# lichtenstein_pwm_v2.net
KiCad netlist of a schematic drawn in EAGLE
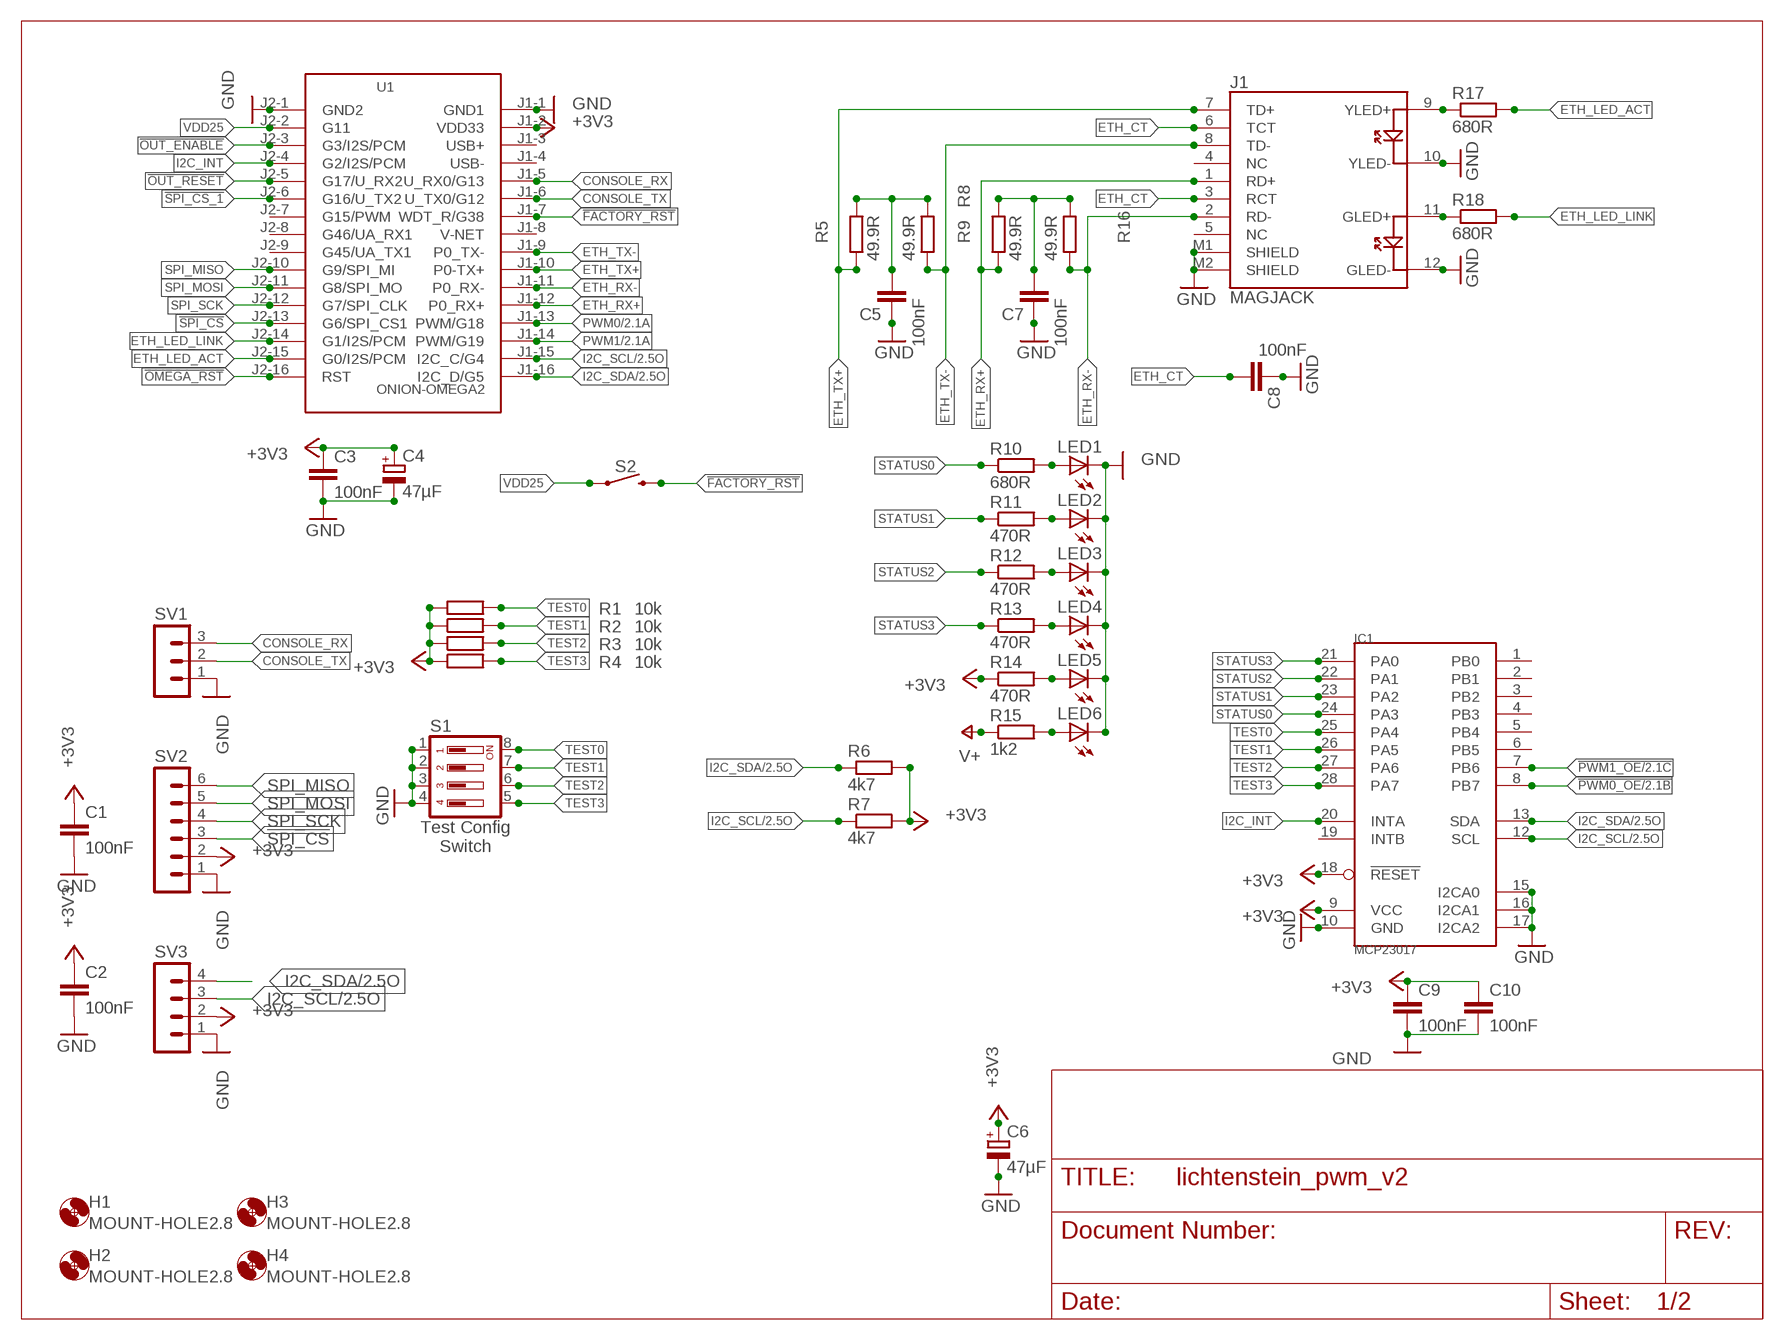
[diagram p0: schematic, sheet 1]
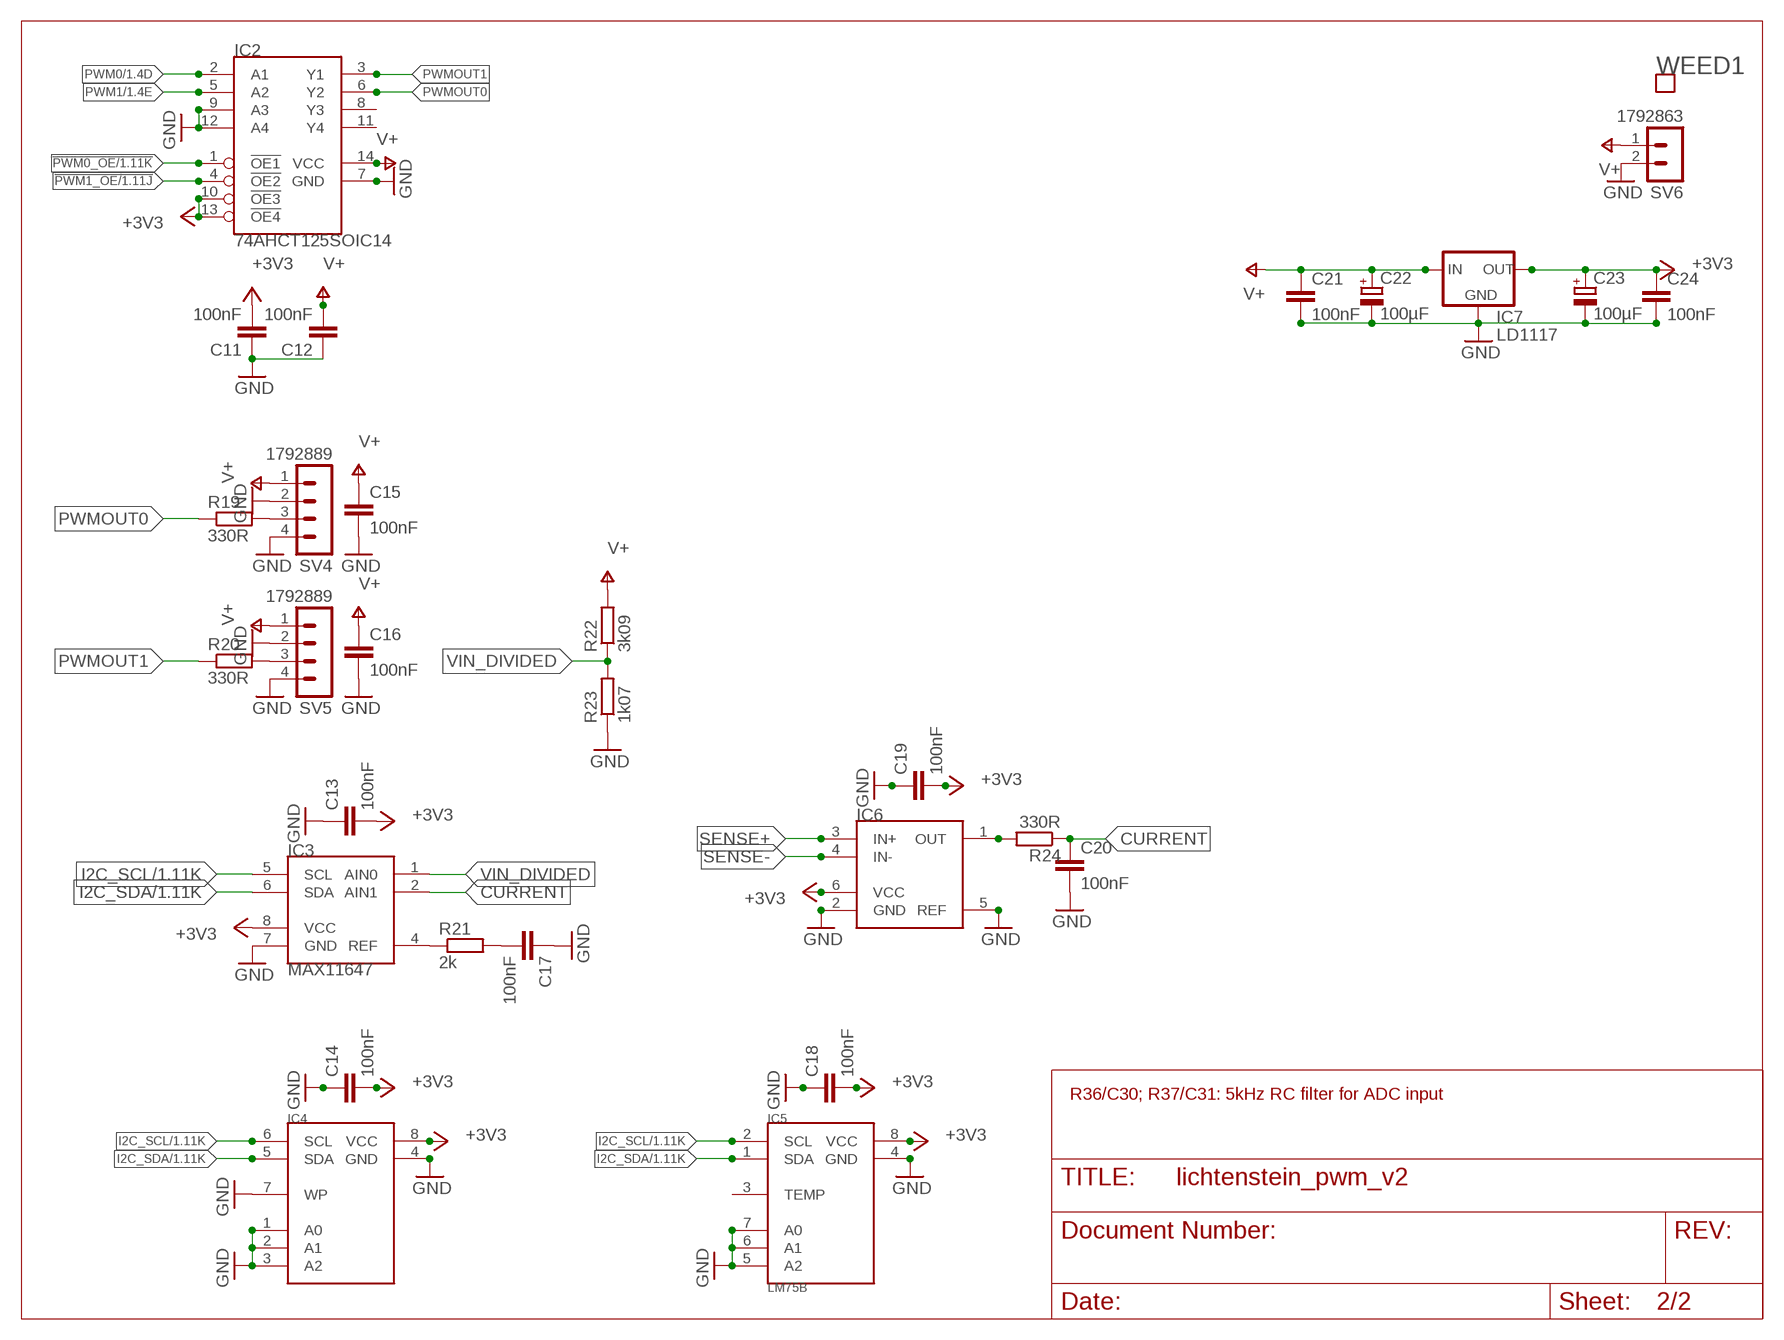
[diagram p1: schematic, sheet 2]

(export (version "E")
  (design (tool "Eeschema 10.0.6"))
  (components
    (comp (ref "C1")
      (value "100nF")
      (footprint "eagle-import:C0805")
      (libsource (lib "eagle-import") (part "C-EUC0805"))
    )
    (comp (ref "C2")
      (value "100nF")
      (footprint "eagle-import:C0805")
      (libsource (lib "eagle-import") (part "C-EUC0805"))
    )
    (comp (ref "C3")
      (value "100nF")
      (footprint "eagle-import:C0805")
      (libsource (lib "eagle-import") (part "C-EUC0805"))
    )
    (comp (ref "C4")
      (value "47µF")
      (footprint "eagle-import:SMC_C")
      (libsource (lib "eagle-import") (part "CPOL-EUSMCC"))
    )
    (comp (ref "C5")
      (value "100nF")
      (footprint "eagle-import:C0805")
      (libsource (lib "eagle-import") (part "C-EUC0805"))
    )
    (comp (ref "C6")
      (value "47µF")
      (footprint "eagle-import:SMC_C")
      (libsource (lib "eagle-import") (part "CPOL-EUSMCC"))
    )
    (comp (ref "C7")
      (value "100nF")
      (footprint "eagle-import:C0805")
      (libsource (lib "eagle-import") (part "C-EUC0805"))
    )
    (comp (ref "C8")
      (value "100nF")
      (footprint "eagle-import:C0805")
      (libsource (lib "eagle-import") (part "C-EUC0805"))
    )
    (comp (ref "C9")
      (value "100nF")
      (footprint "eagle-import:C0805")
      (libsource (lib "eagle-import") (part "C-EUC0805"))
    )
    (comp (ref "C10")
      (value "100nF")
      (footprint "eagle-import:C0805")
      (libsource (lib "eagle-import") (part "C-EUC0805"))
    )
    (comp (ref "H1")
      (value "MOUNT-HOLE2.8")
      (footprint "eagle-import:2,8")
      (libsource (lib "eagle-import") (part "MOUNT-HOLE2.8"))
    )
    (comp (ref "H2")
      (value "MOUNT-HOLE2.8")
      (footprint "eagle-import:2,8")
      (libsource (lib "eagle-import") (part "MOUNT-HOLE2.8"))
    )
    (comp (ref "H3")
      (value "MOUNT-HOLE2.8")
      (footprint "eagle-import:2,8")
      (libsource (lib "eagle-import") (part "MOUNT-HOLE2.8"))
    )
    (comp (ref "H4")
      (value "MOUNT-HOLE2.8")
      (footprint "eagle-import:2,8")
      (libsource (lib "eagle-import") (part "MOUNT-HOLE2.8"))
    )
    (comp (ref "IC1")
      (value "MCP23017")
      (footprint "eagle-import:SO28W")
      (libsource (lib "eagle-import") (part "MCP23017SOIC28"))
    )
    (comp (ref "J1")
      (value "MAGJACK")
      (footprint "eagle-import:MAGJACK")
      (libsource (lib "eagle-import") (part "MAGJACK"))
    )
    (comp (ref "LED1")
      (value "LEDCHIPLED_1206")
      (footprint "eagle-import:CHIPLED_1206")
      (libsource (lib "eagle-import") (part "LEDCHIPLED_1206"))
    )
    (comp (ref "LED2")
      (value "LEDCHIPLED_1206")
      (footprint "eagle-import:CHIPLED_1206")
      (libsource (lib "eagle-import") (part "LEDCHIPLED_1206"))
    )
    (comp (ref "LED3")
      (value "LEDCHIPLED_1206")
      (footprint "eagle-import:CHIPLED_1206")
      (libsource (lib "eagle-import") (part "LEDCHIPLED_1206"))
    )
    (comp (ref "LED4")
      (value "LEDCHIPLED_1206")
      (footprint "eagle-import:CHIPLED_1206")
      (libsource (lib "eagle-import") (part "LEDCHIPLED_1206"))
    )
    (comp (ref "LED5")
      (value "LEDCHIPLED_1206")
      (footprint "eagle-import:CHIPLED_1206")
      (libsource (lib "eagle-import") (part "LEDCHIPLED_1206"))
    )
    (comp (ref "LED6")
      (value "LEDCHIPLED_1206")
      (footprint "eagle-import:CHIPLED_1206")
      (libsource (lib "eagle-import") (part "LEDCHIPLED_1206"))
    )
    (comp (ref "R1")
      (value "10k")
      (footprint "eagle-import:M0805")
      (libsource (lib "eagle-import") (part "R-EU_M0805"))
    )
    (comp (ref "R2")
      (value "10k")
      (footprint "eagle-import:M0805")
      (libsource (lib "eagle-import") (part "R-EU_M0805"))
    )
    (comp (ref "R3")
      (value "10k")
      (footprint "eagle-import:M0805")
      (libsource (lib "eagle-import") (part "R-EU_M0805"))
    )
    (comp (ref "R4")
      (value "10k")
      (footprint "eagle-import:M0805")
      (libsource (lib "eagle-import") (part "R-EU_M0805"))
    )
    (comp (ref "R5")
      (value "49.9R")
      (footprint "eagle-import:M0805")
      (libsource (lib "eagle-import") (part "R-EU_M0805"))
    )
    (comp (ref "R6")
      (value "4k7")
      (footprint "eagle-import:M0805")
      (libsource (lib "eagle-import") (part "R-EU_M0805"))
    )
    (comp (ref "R7")
      (value "4k7")
      (footprint "eagle-import:M0805")
      (libsource (lib "eagle-import") (part "R-EU_M0805"))
    )
    (comp (ref "R8")
      (value "49.9R")
      (footprint "eagle-import:M0805")
      (libsource (lib "eagle-import") (part "R-EU_M0805"))
    )
    (comp (ref "R9")
      (value "49.9R")
      (footprint "eagle-import:M0805")
      (libsource (lib "eagle-import") (part "R-EU_M0805"))
    )
    (comp (ref "R10")
      (value "680R")
      (footprint "eagle-import:M0805")
      (libsource (lib "eagle-import") (part "R-EU_M0805"))
    )
    (comp (ref "R11")
      (value "470R")
      (footprint "eagle-import:M0805")
      (libsource (lib "eagle-import") (part "R-EU_M0805"))
    )
    (comp (ref "R12")
      (value "470R")
      (footprint "eagle-import:M0805")
      (libsource (lib "eagle-import") (part "R-EU_M0805"))
    )
    (comp (ref "R13")
      (value "470R")
      (footprint "eagle-import:M0805")
      (libsource (lib "eagle-import") (part "R-EU_M0805"))
    )
    (comp (ref "R14")
      (value "470R")
      (footprint "eagle-import:M0805")
      (libsource (lib "eagle-import") (part "R-EU_M0805"))
    )
    (comp (ref "R15")
      (value "1k2")
      (footprint "eagle-import:M0805")
      (libsource (lib "eagle-import") (part "R-EU_M0805"))
    )
    (comp (ref "R16")
      (value "49.9R")
      (footprint "eagle-import:M0805")
      (libsource (lib "eagle-import") (part "R-EU_M0805"))
    )
    (comp (ref "R17")
      (value "680R")
      (footprint "eagle-import:M0805")
      (libsource (lib "eagle-import") (part "R-EU_M0805"))
    )
    (comp (ref "R18")
      (value "680R")
      (footprint "eagle-import:M0805")
      (libsource (lib "eagle-import") (part "R-EU_M0805"))
    )
    (comp (ref "S1")
      (value "219-04")
      (footprint "eagle-import:CTS-219-04")
      (libsource (lib "eagle-import") (part "219-04"))
    )
    (comp (ref "S2")
      (value "MOMENTARY-SWITCH-SPST-PTH-6.0MM")
      (footprint "eagle-import:TACTILE_SWITCH_PTH_6.0MM")
      (libsource (lib "eagle-import") (part "MOMENTARY-SWITCH-SPST-PTH-6.0MM"))
    )
    (comp (ref "SV1")
      (value "MA03-1")
      (footprint "eagle-import:MA03-1")
      (libsource (lib "eagle-import") (part "MA03-1"))
    )
    (comp (ref "SV2")
      (value "MA06-1")
      (footprint "eagle-import:MA06-1")
      (libsource (lib "eagle-import") (part "MA06-1"))
    )
    (comp (ref "SV3")
      (value "MA04-1")
      (footprint "eagle-import:MA04-1")
      (libsource (lib "eagle-import") (part "MA04-1"))
    )
    (comp (ref "U1")
      (value "ONION-OMEGA2")
      (footprint "eagle-import:ONION-2MM-2X16")
      (libsource (lib "eagle-import") (part "ONION-OMEGA2"))
    )
    (comp (ref "C11")
      (value "100nF")
      (footprint "eagle-import:C0805")
      (libsource (lib "eagle-import") (part "C-EUC0805"))
    )
    (comp (ref "C12")
      (value "100nF")
      (footprint "eagle-import:C0805")
      (libsource (lib "eagle-import") (part "C-EUC0805"))
    )
    (comp (ref "C13")
      (value "100nF")
      (footprint "eagle-import:C0805")
      (libsource (lib "eagle-import") (part "C-EUC0805"))
    )
    (comp (ref "C14")
      (value "100nF")
      (footprint "eagle-import:C0805")
      (libsource (lib "eagle-import") (part "C-EUC0805"))
    )
    (comp (ref "C15")
      (value "100nF")
      (footprint "eagle-import:C0805")
      (libsource (lib "eagle-import") (part "C-EUC0805"))
    )
    (comp (ref "C16")
      (value "100nF")
      (footprint "eagle-import:C0805")
      (libsource (lib "eagle-import") (part "C-EUC0805"))
    )
    (comp (ref "C17")
      (value "100nF")
      (footprint "eagle-import:C0805")
      (libsource (lib "eagle-import") (part "C-EUC0805"))
    )
    (comp (ref "C18")
      (value "100nF")
      (footprint "eagle-import:C0805")
      (libsource (lib "eagle-import") (part "C-EUC0805"))
    )
    (comp (ref "C19")
      (value "100nF")
      (footprint "eagle-import:C0805")
      (libsource (lib "eagle-import") (part "C-EUC0805"))
    )
    (comp (ref "C20")
      (value "100nF")
      (footprint "eagle-import:C0805")
      (libsource (lib "eagle-import") (part "C-EUC0805"))
    )
    (comp (ref "C21")
      (value "100nF")
      (footprint "eagle-import:C0805")
      (libsource (lib "eagle-import") (part "C-EUC0805"))
    )
    (comp (ref "C22")
      (value "100µF")
      (footprint "eagle-import:PANASONIC_D")
      (libsource (lib "eagle-import") (part "CPOL-EUD"))
    )
    (comp (ref "C23")
      (value "100µF")
      (footprint "eagle-import:CT7343")
      (libsource (lib "eagle-import") (part "CPOL-EUCT7343"))
    )
    (comp (ref "C24")
      (value "100nF")
      (footprint "eagle-import:C0805")
      (libsource (lib "eagle-import") (part "C-EUC0805"))
    )
    (comp (ref "IC2")
      (value "74AHCT125SOIC14")
      (footprint "eagle-import:SO14")
      (libsource (lib "eagle-import") (part "74AHCT125SOIC14"))
    )
    (comp (ref "IC3")
      (value "MAX11647")
      (footprint "eagle-import:UMAX8")
      (libsource (lib "eagle-import") (part "MAX11647UMAX-8"))
    )
    (comp (ref "IC4")
      (value "AT24C02DSOIC-8")
      (footprint "eagle-import:SOIC8")
      (libsource (lib "eagle-import") (part "AT24C02DSOIC-8"))
    )
    (comp (ref "IC5")
      (value "LM75B")
      (footprint "eagle-import:SOIC8")
      (libsource (lib "eagle-import") (part "LM75B"))
    )
    (comp (ref "IC6")
      (value "INA18120VVSOT-23")
      (footprint "eagle-import:SOT23-6L")
      (libsource (lib "eagle-import") (part "INA181SOT-2320VV"))
    )
    (comp (ref "IC7")
      (value "LD1117")
      (footprint "eagle-import:TO220V")
      (libsource (lib "eagle-import") (part "LD1117TO-220"))
    )
    (comp (ref "R19")
      (value "330R")
      (footprint "eagle-import:M0805")
      (libsource (lib "eagle-import") (part "R-EU_M0805"))
    )
    (comp (ref "R20")
      (value "330R")
      (footprint "eagle-import:M0805")
      (libsource (lib "eagle-import") (part "R-EU_M0805"))
    )
    (comp (ref "R21")
      (value "2k")
      (footprint "eagle-import:M0805")
      (libsource (lib "eagle-import") (part "R-EU_M0805"))
    )
    (comp (ref "R22")
      (value "3k09")
      (footprint "eagle-import:M0805")
      (libsource (lib "eagle-import") (part "R-EU_M0805"))
    )
    (comp (ref "R23")
      (value "1k07")
      (footprint "eagle-import:M0805")
      (libsource (lib "eagle-import") (part "R-EU_M0805"))
    )
    (comp (ref "R24")
      (value "330R")
      (footprint "eagle-import:M0805")
      (libsource (lib "eagle-import") (part "R-EU_M0805"))
    )
    (comp (ref "SV4")
      (value "1792889")
      (footprint "eagle-import:1792889")
      (libsource (lib "eagle-import") (part "1792889"))
    )
    (comp (ref "SV5")
      (value "1792889")
      (footprint "eagle-import:1792889")
      (libsource (lib "eagle-import") (part "1792889"))
    )
    (comp (ref "SV6")
      (value "1792863")
      (footprint "eagle-import:1792863")
      (libsource (lib "eagle-import") (part "1792863"))
    )
    (comp (ref "WEED1")
      (value "WEED")
      (footprint "eagle-import:DOINK")
      (libsource (lib "eagle-import") (part "WEED"))
    )
  )
  (nets
    (net (code "1") (name "+3V3") (class "Default")
      (node (ref "C1") (pin "1") (pinfunction "1_1") (pintype "passive"))
      (node (ref "C10") (pin "1") (pinfunction "1_1") (pintype "passive"))
      (node (ref "C11") (pin "2") (pinfunction "2_2") (pintype "passive"))
      (node (ref "C13") (pin "2") (pinfunction "2_2") (pintype "passive"))
      (node (ref "C14") (pin "2") (pinfunction "2_2") (pintype "passive"))
      (node (ref "C18") (pin "2") (pinfunction "2_2") (pintype "passive"))
      (node (ref "C19") (pin "2") (pinfunction "2_2") (pintype "passive"))
      (node (ref "C2") (pin "1") (pinfunction "1_1") (pintype "passive"))
      (node (ref "C23") (pin "+") (pinfunction "+_+") (pintype "passive"))
      (node (ref "C24") (pin "1") (pinfunction "1_1") (pintype "passive"))
      (node (ref "C3") (pin "1") (pinfunction "1_1") (pintype "passive"))
      (node (ref "C4") (pin "+") (pinfunction "+_+") (pintype "passive"))
      (node (ref "C6") (pin "+") (pinfunction "+_+") (pintype "passive"))
      (node (ref "C9") (pin "1") (pinfunction "1_1") (pintype "passive"))
      (node (ref "IC1") (pin "18") (pinfunction "~{RESET}_18") (pintype "input"))
      (node (ref "IC1") (pin "9") (pinfunction "VCC_9") (pintype "power_in"))
      (node (ref "IC2") (pin "10") (pinfunction "~{OE3}_10") (pintype "input"))
      (node (ref "IC2") (pin "13") (pinfunction "~{OE4}_13") (pintype "input"))
      (node (ref "IC3") (pin "8") (pinfunction "VCC_8") (pintype "power_in"))
      (node (ref "IC4") (pin "8") (pinfunction "VCC_8") (pintype "power_in"))
      (node (ref "IC5") (pin "8") (pinfunction "VCC_8") (pintype "power_in"))
      (node (ref "IC6") (pin "6") (pinfunction "VCC_6") (pintype "power_in"))
      (node (ref "IC7") (pin "2") (pinfunction "OUT_2") (pintype "passive"))
      (node (ref "R1") (pin "1") (pinfunction "1_1") (pintype "passive"))
      (node (ref "R14") (pin "1") (pinfunction "1_1") (pintype "passive"))
      (node (ref "R2") (pin "1") (pinfunction "1_1") (pintype "passive"))
      (node (ref "R3") (pin "1") (pinfunction "1_1") (pintype "passive"))
      (node (ref "R4") (pin "1") (pinfunction "1_1") (pintype "passive"))
      (node (ref "R6") (pin "2") (pinfunction "2_2") (pintype "passive"))
      (node (ref "R7") (pin "2") (pinfunction "2_2") (pintype "passive"))
      (node (ref "SV2") (pin "2") (pinfunction "2_2") (pintype "passive"))
      (node (ref "SV3") (pin "2") (pinfunction "2_2") (pintype "passive"))
      (node (ref "U1") (pin "J1-2") (pinfunction "VDD33_J1-2") (pintype "bidirectional"))
    )
    (net (code "2") (name "CONSOLE_RX") (class "Default")
      (node (ref "SV1") (pin "3") (pinfunction "3_3") (pintype "passive"))
      (node (ref "U1") (pin "J1-5") (pinfunction "U_RX0/G13_J1-5") (pintype "bidirectional"))
    )
    (net (code "3") (name "CONSOLE_TX") (class "Default")
      (node (ref "SV1") (pin "2") (pinfunction "2_2") (pintype "passive"))
      (node (ref "U1") (pin "J1-6") (pinfunction "U_TX0/G12_J1-6") (pintype "bidirectional"))
    )
    (net (code "4") (name "CURRENT") (class "Default")
      (node (ref "C20") (pin "1") (pinfunction "1_1") (pintype "passive"))
      (node (ref "IC3") (pin "2") (pinfunction "AIN1_2") (pintype "input"))
      (node (ref "R24") (pin "1") (pinfunction "1_1") (pintype "passive"))
    )
    (net (code "5") (name "ETH_CT") (class "Default")
      (node (ref "C8") (pin "2") (pinfunction "2_2") (pintype "passive"))
      (node (ref "J1") (pin "3") (pinfunction "RCT_3") (pintype "bidirectional"))
      (node (ref "J1") (pin "6") (pinfunction "TCT_6") (pintype "bidirectional"))
    )
    (net (code "6") (name "ETH_LED_ACT") (class "Default")
      (node (ref "R17") (pin "2") (pinfunction "2_2") (pintype "passive"))
      (node (ref "U1") (pin "J2-15") (pinfunction "G0/I2S/PCM_J2-15") (pintype "bidirectional"))
    )
    (net (code "7") (name "ETH_LED_LINK") (class "Default")
      (node (ref "R18") (pin "2") (pinfunction "2_2") (pintype "passive"))
      (node (ref "U1") (pin "J2-14") (pinfunction "G1/I2S/PCM_J2-14") (pintype "bidirectional"))
    )
    (net (code "8") (name "ETH_RX+") (class "Default")
      (node (ref "J1") (pin "1") (pinfunction "RD+_1") (pintype "bidirectional"))
      (node (ref "R9") (pin "1") (pinfunction "1_1") (pintype "passive"))
      (node (ref "U1") (pin "J1-12") (pinfunction "P0_RX+_J1-12") (pintype "bidirectional"))
    )
    (net (code "9") (name "ETH_RX-") (class "Default")
      (node (ref "J1") (pin "2") (pinfunction "RD-_2") (pintype "bidirectional"))
      (node (ref "R16") (pin "1") (pinfunction "1_1") (pintype "passive"))
      (node (ref "U1") (pin "J1-11") (pinfunction "P0_RX-_J1-11") (pintype "bidirectional"))
    )
    (net (code "10") (name "ETH_TX+") (class "Default")
      (node (ref "J1") (pin "7") (pinfunction "TD+_7") (pintype "bidirectional"))
      (node (ref "R5") (pin "1") (pinfunction "1_1") (pintype "passive"))
      (node (ref "U1") (pin "J1-10") (pinfunction "P0-TX+_J1-10") (pintype "bidirectional"))
    )
    (net (code "11") (name "ETH_TX-") (class "Default")
      (node (ref "J1") (pin "8") (pinfunction "TD-_8") (pintype "bidirectional"))
      (node (ref "R8") (pin "1") (pinfunction "1_1") (pintype "passive"))
      (node (ref "U1") (pin "J1-9") (pinfunction "P0_TX-_J1-9") (pintype "bidirectional"))
    )
    (net (code "12") (name "GND") (class "Default")
      (node (ref "C1") (pin "2") (pinfunction "2_2") (pintype "passive"))
      (node (ref "C10") (pin "2") (pinfunction "2_2") (pintype "passive"))
      (node (ref "C11") (pin "1") (pinfunction "1_1") (pintype "passive"))
      (node (ref "C12") (pin "1") (pinfunction "1_1") (pintype "passive"))
      (node (ref "C13") (pin "1") (pinfunction "1_1") (pintype "passive"))
      (node (ref "C14") (pin "1") (pinfunction "1_1") (pintype "passive"))
      (node (ref "C15") (pin "2") (pinfunction "2_2") (pintype "passive"))
      (node (ref "C16") (pin "2") (pinfunction "2_2") (pintype "passive"))
      (node (ref "C17") (pin "1") (pinfunction "1_1") (pintype "passive"))
      (node (ref "C18") (pin "1") (pinfunction "1_1") (pintype "passive"))
      (node (ref "C19") (pin "1") (pinfunction "1_1") (pintype "passive"))
      (node (ref "C2") (pin "2") (pinfunction "2_2") (pintype "passive"))
      (node (ref "C20") (pin "2") (pinfunction "2_2") (pintype "passive"))
      (node (ref "C21") (pin "2") (pinfunction "2_2") (pintype "passive"))
      (node (ref "C22") (pin "-") (pinfunction "-_-") (pintype "passive"))
      (node (ref "C23") (pin "-") (pinfunction "-_-") (pintype "passive"))
      (node (ref "C24") (pin "2") (pinfunction "2_2") (pintype "passive"))
      (node (ref "C3") (pin "2") (pinfunction "2_2") (pintype "passive"))
      (node (ref "C4") (pin "-") (pinfunction "-_-") (pintype "passive"))
      (node (ref "C5") (pin "1") (pinfunction "1_1") (pintype "passive"))
      (node (ref "C6") (pin "-") (pinfunction "-_-") (pintype "passive"))
      (node (ref "C7") (pin "1") (pinfunction "1_1") (pintype "passive"))
      (node (ref "C8") (pin "1") (pinfunction "1_1") (pintype "passive"))
      (node (ref "C9") (pin "2") (pinfunction "2_2") (pintype "passive"))
      (node (ref "IC1") (pin "10") (pinfunction "GND_10") (pintype "power_in"))
      (node (ref "IC1") (pin "15") (pinfunction "I2CA0_15") (pintype "bidirectional"))
      (node (ref "IC1") (pin "16") (pinfunction "I2CA1_16") (pintype "bidirectional"))
      (node (ref "IC1") (pin "17") (pinfunction "I2CA2_17") (pintype "bidirectional"))
      (node (ref "IC2") (pin "12") (pinfunction "A4_12") (pintype "input"))
      (node (ref "IC2") (pin "7") (pinfunction "GND_7") (pintype "power_in"))
      (node (ref "IC2") (pin "9") (pinfunction "A3_9") (pintype "input"))
      (node (ref "IC3") (pin "7") (pinfunction "GND_7") (pintype "power_in"))
      (node (ref "IC4") (pin "1") (pinfunction "A0_1") (pintype "bidirectional"))
      (node (ref "IC4") (pin "2") (pinfunction "A1_2") (pintype "bidirectional"))
      (node (ref "IC4") (pin "3") (pinfunction "A2_3") (pintype "bidirectional"))
      (node (ref "IC4") (pin "4") (pinfunction "GND_4") (pintype "power_in"))
      (node (ref "IC4") (pin "7") (pinfunction "WP_7") (pintype "bidirectional"))
      (node (ref "IC5") (pin "4") (pinfunction "GND_4") (pintype "power_in"))
      (node (ref "IC5") (pin "5") (pinfunction "A2_5") (pintype "bidirectional"))
      (node (ref "IC5") (pin "6") (pinfunction "A1_6") (pintype "bidirectional"))
      (node (ref "IC5") (pin "7") (pinfunction "A0_7") (pintype "bidirectional"))
      (node (ref "IC6") (pin "2") (pinfunction "GND_2") (pintype "power_in"))
      (node (ref "IC6") (pin "5") (pinfunction "REF_5") (pintype "output"))
      (node (ref "IC7") (pin "1") (pinfunction "GND_1") (pintype "input"))
      (node (ref "J1") (pin "10") (pinfunction "YLED-_10") (pintype "bidirectional"))
      (node (ref "J1") (pin "12") (pinfunction "GLED-_12") (pintype "bidirectional"))
      (node (ref "J1") (pin "M1") (pinfunction "SHIELD_M1") (pintype "bidirectional"))
      (node (ref "J1") (pin "M2") (pinfunction "SHIELD_M2") (pintype "bidirectional"))
      (node (ref "LED1") (pin "C") (pinfunction "C_C") (pintype "passive"))
      (node (ref "LED2") (pin "C") (pinfunction "C_C") (pintype "passive"))
      (node (ref "LED3") (pin "C") (pinfunction "C_C") (pintype "passive"))
      (node (ref "LED4") (pin "C") (pinfunction "C_C") (pintype "passive"))
      (node (ref "LED5") (pin "C") (pinfunction "C_C") (pintype "passive"))
      (node (ref "LED6") (pin "C") (pinfunction "C_C") (pintype "passive"))
      (node (ref "R23") (pin "1") (pinfunction "1_1") (pintype "passive"))
      (node (ref "S1") (pin "1") (pinfunction "1_1") (pintype "passive"))
      (node (ref "S1") (pin "2") (pinfunction "2_2") (pintype "passive"))
      (node (ref "S1") (pin "3") (pinfunction "3_3") (pintype "passive"))
      (node (ref "S1") (pin "4") (pinfunction "4_4") (pintype "passive"))
      (node (ref "SV1") (pin "1") (pinfunction "1_1") (pintype "passive"))
      (node (ref "SV2") (pin "1") (pinfunction "1_1") (pintype "passive"))
      (node (ref "SV3") (pin "1") (pinfunction "1_1") (pintype "passive"))
      (node (ref "SV4") (pin "2") (pinfunction "2_2") (pintype "passive"))
      (node (ref "SV4") (pin "4") (pinfunction "4_4") (pintype "passive"))
      (node (ref "SV5") (pin "2") (pinfunction "2_2") (pintype "passive"))
      (node (ref "SV5") (pin "4") (pinfunction "4_4") (pintype "passive"))
      (node (ref "SV6") (pin "2") (pinfunction "2_2") (pintype "passive"))
      (node (ref "U1") (pin "J1-1") (pinfunction "GND1_J1-1") (pintype "bidirectional"))
      (node (ref "U1") (pin "J2-1") (pinfunction "GND2_J2-1") (pintype "bidirectional"))
    )
    (net (code "13") (name "I2C_INT") (class "Default")
      (node (ref "IC1") (pin "20") (pinfunction "INTA_20") (pintype "output"))
      (node (ref "U1") (pin "J2-4") (pinfunction "G2/I2S/PCM_J2-4") (pintype "bidirectional"))
    )
    (net (code "14") (name "I2C_SCL") (class "Default")
      (node (ref "IC1") (pin "12") (pinfunction "SCL_12") (pintype "bidirectional"))
      (node (ref "IC3") (pin "5") (pinfunction "SCL_5") (pintype "bidirectional"))
      (node (ref "IC4") (pin "6") (pinfunction "SCL_6") (pintype "bidirectional"))
      (node (ref "IC5") (pin "2") (pinfunction "SCL_2") (pintype "bidirectional"))
      (node (ref "R7") (pin "1") (pinfunction "1_1") (pintype "passive"))
      (node (ref "SV3") (pin "3") (pinfunction "3_3") (pintype "passive"))
      (node (ref "U1") (pin "J1-15") (pinfunction "I2C_C/G4_J1-15") (pintype "bidirectional"))
    )
    (net (code "15") (name "I2C_SDA") (class "Default")
      (node (ref "IC1") (pin "13") (pinfunction "SDA_13") (pintype "bidirectional"))
      (node (ref "IC3") (pin "6") (pinfunction "SDA_6") (pintype "bidirectional"))
      (node (ref "IC4") (pin "5") (pinfunction "SDA_5") (pintype "bidirectional"))
      (node (ref "IC5") (pin "1") (pinfunction "SDA_1") (pintype "bidirectional"))
      (node (ref "R6") (pin "1") (pinfunction "1_1") (pintype "passive"))
      (node (ref "SV3") (pin "4") (pinfunction "4_4") (pintype "passive"))
      (node (ref "U1") (pin "J1-16") (pinfunction "I2C_D/G5_J1-16") (pintype "bidirectional"))
    )
    (net (code "16") (name "Net-(C5-Pad2)") (class "Default")
      (node (ref "C5") (pin "2") (pinfunction "2_2") (pintype "passive"))
      (node (ref "R5") (pin "2") (pinfunction "2_2") (pintype "passive"))
      (node (ref "R8") (pin "2") (pinfunction "2_2") (pintype "passive"))
    )
    (net (code "17") (name "Net-(C7-Pad2)") (class "Default")
      (node (ref "C7") (pin "2") (pinfunction "2_2") (pintype "passive"))
      (node (ref "R16") (pin "2") (pinfunction "2_2") (pintype "passive"))
      (node (ref "R9") (pin "2") (pinfunction "2_2") (pintype "passive"))
    )
    (net (code "18") (name "Net-(C17-Pad2)") (class "Default")
      (node (ref "C17") (pin "2") (pinfunction "2_2") (pintype "passive"))
      (node (ref "R21") (pin "2") (pinfunction "2_2") (pintype "passive"))
    )
    (net (code "19") (name "Net-(IC3-REF)") (class "Default")
      (node (ref "IC3") (pin "4") (pinfunction "REF_4") (pintype "input"))
      (node (ref "R21") (pin "1") (pinfunction "1_1") (pintype "passive"))
    )
    (net (code "20") (name "Net-(IC6-OUT)") (class "Default")
      (node (ref "IC6") (pin "1") (pinfunction "OUT_1") (pintype "output"))
      (node (ref "R24") (pin "2") (pinfunction "2_2") (pintype "passive"))
    )
    (net (code "21") (name "Net-(J1-GLED+)") (class "Default")
      (node (ref "J1") (pin "11") (pinfunction "GLED+_11") (pintype "bidirectional"))
      (node (ref "R18") (pin "1") (pinfunction "1_1") (pintype "passive"))
    )
    (net (code "22") (name "Net-(J1-YLED+)") (class "Default")
      (node (ref "J1") (pin "9") (pinfunction "YLED+_9") (pintype "bidirectional"))
      (node (ref "R17") (pin "1") (pinfunction "1_1") (pintype "passive"))
    )
    (net (code "23") (name "Net-(LED1-PadA)") (class "Default")
      (node (ref "LED1") (pin "A") (pinfunction "A_A") (pintype "passive"))
      (node (ref "R10") (pin "2") (pinfunction "2_2") (pintype "passive"))
    )
    (net (code "24") (name "Net-(LED2-PadA)") (class "Default")
      (node (ref "LED2") (pin "A") (pinfunction "A_A") (pintype "passive"))
      (node (ref "R11") (pin "2") (pinfunction "2_2") (pintype "passive"))
    )
    (net (code "25") (name "Net-(LED3-PadA)") (class "Default")
      (node (ref "LED3") (pin "A") (pinfunction "A_A") (pintype "passive"))
      (node (ref "R12") (pin "2") (pinfunction "2_2") (pintype "passive"))
    )
    (net (code "26") (name "Net-(LED4-PadA)") (class "Default")
      (node (ref "LED4") (pin "A") (pinfunction "A_A") (pintype "passive"))
      (node (ref "R13") (pin "2") (pinfunction "2_2") (pintype "passive"))
    )
    (net (code "27") (name "Net-(LED5-PadA)") (class "Default")
      (node (ref "LED5") (pin "A") (pinfunction "A_A") (pintype "passive"))
      (node (ref "R14") (pin "2") (pinfunction "2_2") (pintype "passive"))
    )
    (net (code "28") (name "Net-(LED6-PadA)") (class "Default")
      (node (ref "LED6") (pin "A") (pinfunction "A_A") (pintype "passive"))
      (node (ref "R15") (pin "2") (pinfunction "2_2") (pintype "passive"))
    )
    (net (code "29") (name "Net-(R19-Pad2)") (class "Default")
      (node (ref "R19") (pin "2") (pinfunction "2_2") (pintype "passive"))
      (node (ref "SV4") (pin "3") (pinfunction "3_3") (pintype "passive"))
    )
    (net (code "30") (name "Net-(R20-Pad2)") (class "Default")
      (node (ref "R20") (pin "2") (pinfunction "2_2") (pintype "passive"))
      (node (ref "SV5") (pin "3") (pinfunction "3_3") (pintype "passive"))
    )
    (net (code "31") (name "PWM0") (class "Default")
      (node (ref "IC2") (pin "2") (pinfunction "A1_2") (pintype "input"))
      (node (ref "U1") (pin "J1-13") (pinfunction "PWM/G18_J1-13") (pintype "bidirectional"))
    )
    (net (code "32") (name "PWM1") (class "Default")
      (node (ref "IC2") (pin "5") (pinfunction "A2_5") (pintype "input"))
      (node (ref "U1") (pin "J1-14") (pinfunction "PWM/G19_J1-14") (pintype "bidirectional"))
    )
    (net (code "33") (name "PWMOUT0") (class "Default")
      (node (ref "IC2") (pin "6") (pinfunction "Y2_6") (pintype "output"))
      (node (ref "R19") (pin "1") (pinfunction "1_1") (pintype "passive"))
    )
    (net (code "34") (name "PWMOUT1") (class "Default")
      (node (ref "IC2") (pin "3") (pinfunction "Y1_3") (pintype "output"))
      (node (ref "R20") (pin "1") (pinfunction "1_1") (pintype "passive"))
    )
    (net (code "35") (name "SENSE+") (class "Default")
      (node (ref "IC6") (pin "3") (pinfunction "IN+_3") (pintype "passive"))
    )
    (net (code "36") (name "SENSE-") (class "Default")
      (node (ref "IC6") (pin "4") (pinfunction "IN-_4") (pintype "passive"))
    )
    (net (code "37") (name "SPI_MISO") (class "Default")
      (node (ref "SV2") (pin "6") (pinfunction "6_6") (pintype "passive"))
      (node (ref "U1") (pin "J2-10") (pinfunction "G9/SPI_MI_J2-10") (pintype "bidirectional"))
    )
    (net (code "38") (name "SPI_MOSI") (class "Default")
      (node (ref "SV2") (pin "5") (pinfunction "5_5") (pintype "passive"))
      (node (ref "U1") (pin "J2-11") (pinfunction "G8/SPI_MO_J2-11") (pintype "bidirectional"))
    )
    (net (code "39") (name "SPI_SCK") (class "Default")
      (node (ref "SV2") (pin "4") (pinfunction "4_4") (pintype "passive"))
      (node (ref "U1") (pin "J2-12") (pinfunction "G7/SPI_CLK_J2-12") (pintype "bidirectional"))
    )
    (net (code "40") (name "STATUS0") (class "Default")
      (node (ref "IC1") (pin "24") (pinfunction "PA3_24") (pintype "bidirectional"))
      (node (ref "R10") (pin "1") (pinfunction "1_1") (pintype "passive"))
    )
    (net (code "41") (name "STATUS1") (class "Default")
      (node (ref "IC1") (pin "23") (pinfunction "PA2_23") (pintype "bidirectional"))
      (node (ref "R11") (pin "1") (pinfunction "1_1") (pintype "passive"))
    )
    (net (code "42") (name "STATUS2") (class "Default")
      (node (ref "IC1") (pin "22") (pinfunction "PA1_22") (pintype "bidirectional"))
      (node (ref "R12") (pin "1") (pinfunction "1_1") (pintype "passive"))
    )
    (net (code "43") (name "STATUS3") (class "Default")
      (node (ref "IC1") (pin "21") (pinfunction "PA0_21") (pintype "bidirectional"))
      (node (ref "R13") (pin "1") (pinfunction "1_1") (pintype "passive"))
    )
    (net (code "44") (name "TEST0") (class "Default")
      (node (ref "IC1") (pin "25") (pinfunction "PA4_25") (pintype "bidirectional"))
      (node (ref "R1") (pin "2") (pinfunction "2_2") (pintype "passive"))
      (node (ref "S1") (pin "8") (pinfunction "8_8") (pintype "passive"))
    )
    (net (code "45") (name "TEST1") (class "Default")
      (node (ref "IC1") (pin "26") (pinfunction "PA5_26") (pintype "bidirectional"))
      (node (ref "R2") (pin "2") (pinfunction "2_2") (pintype "passive"))
      (node (ref "S1") (pin "7") (pinfunction "7_7") (pintype "passive"))
    )
    (net (code "46") (name "TEST2") (class "Default")
      (node (ref "IC1") (pin "27") (pinfunction "PA6_27") (pintype "bidirectional"))
      (node (ref "R3") (pin "2") (pinfunction "2_2") (pintype "passive"))
      (node (ref "S1") (pin "6") (pinfunction "6_6") (pintype "passive"))
    )
    (net (code "47") (name "TEST3") (class "Default")
      (node (ref "IC1") (pin "28") (pinfunction "PA7_28") (pintype "bidirectional"))
      (node (ref "R4") (pin "2") (pinfunction "2_2") (pintype "passive"))
      (node (ref "S1") (pin "5") (pinfunction "5_5") (pintype "passive"))
    )
    (net (code "48") (name "V+") (class "Default")
      (node (ref "C12") (pin "2") (pinfunction "2_2") (pintype "passive"))
      (node (ref "C15") (pin "1") (pinfunction "1_1") (pintype "passive"))
      (node (ref "C16") (pin "1") (pinfunction "1_1") (pintype "passive"))
      (node (ref "C21") (pin "1") (pinfunction "1_1") (pintype "passive"))
      (node (ref "C22") (pin "+") (pinfunction "+_+") (pintype "passive"))
      (node (ref "IC2") (pin "14") (pinfunction "VCC_14") (pintype "power_in"))
      (node (ref "IC7") (pin "3") (pinfunction "IN_3") (pintype "input"))
      (node (ref "R15") (pin "1") (pinfunction "1_1") (pintype "passive"))
      (node (ref "R22") (pin "2") (pinfunction "2_2") (pintype "passive"))
      (node (ref "SV4") (pin "1") (pinfunction "1_1") (pintype "passive"))
      (node (ref "SV5") (pin "1") (pinfunction "1_1") (pintype "passive"))
      (node (ref "SV6") (pin "1") (pinfunction "1_1") (pintype "passive"))
    )
    (net (code "49") (name "VDD25") (class "Default")
      (node (ref "S2") (pin "1") (pinfunction "1_1") (pintype "passive"))
      (node (ref "U1") (pin "J2-2") (pinfunction "G11_J2-2") (pintype "bidirectional"))
    )
    (net (code "50") (name "VIN_DIVIDED") (class "Default")
      (node (ref "IC3") (pin "1") (pinfunction "AIN0_1") (pintype "input"))
      (node (ref "R22") (pin "1") (pinfunction "1_1") (pintype "passive"))
      (node (ref "R23") (pin "2") (pinfunction "2_2") (pintype "passive"))
    )
    (net (code "51") (name "unconnected-(IC1-INTB-Pad19)") (class "Default")
      (node (ref "IC1") (pin "19") (pinfunction "INTB_19") (pintype "output"))
    )
    (net (code "52") (name "unconnected-(IC1-PB0-Pad1)") (class "Default")
      (node (ref "IC1") (pin "1") (pinfunction "PB0_1") (pintype "bidirectional"))
    )
    (net (code "53") (name "unconnected-(IC1-PB1-Pad2)") (class "Default")
      (node (ref "IC1") (pin "2") (pinfunction "PB1_2") (pintype "bidirectional"))
    )
    (net (code "54") (name "unconnected-(IC1-PB2-Pad3)") (class "Default")
      (node (ref "IC1") (pin "3") (pinfunction "PB2_3") (pintype "bidirectional"))
    )
    (net (code "55") (name "unconnected-(IC1-PB3-Pad4)") (class "Default")
      (node (ref "IC1") (pin "4") (pinfunction "PB3_4") (pintype "bidirectional"))
    )
    (net (code "56") (name "unconnected-(IC1-PB4-Pad5)") (class "Default")
      (node (ref "IC1") (pin "5") (pinfunction "PB4_5") (pintype "bidirectional"))
    )
    (net (code "57") (name "unconnected-(IC1-PB5-Pad6)") (class "Default")
      (node (ref "IC1") (pin "6") (pinfunction "PB5_6") (pintype "bidirectional"))
    )
    (net (code "58") (name "unconnected-(IC2-Y3-Pad8)") (class "Default")
      (node (ref "IC2") (pin "8") (pinfunction "Y3_8") (pintype "output"))
    )
    (net (code "59") (name "unconnected-(IC2-Y4-Pad11)") (class "Default")
      (node (ref "IC2") (pin "11") (pinfunction "Y4_11") (pintype "output"))
    )
    (net (code "60") (name "unconnected-(IC5-TEMP-Pad3)") (class "Default")
      (node (ref "IC5") (pin "3") (pinfunction "TEMP_3") (pintype "bidirectional"))
    )
    (net (code "61") (name "unconnected-(J1-NC-Pad4)") (class "Default")
      (node (ref "J1") (pin "4") (pinfunction "NC_4") (pintype "bidirectional"))
    )
    (net (code "62") (name "unconnected-(J1-NC-Pad5)") (class "Default")
      (node (ref "J1") (pin "5") (pinfunction "NC_5") (pintype "bidirectional"))
    )
    (net (code "63") (name "unconnected-(U1-G15{slash}PWM-PadJ2-7)") (class "Default")
      (node (ref "U1") (pin "J2-7") (pinfunction "G15/PWM_J2-7") (pintype "bidirectional"))
    )
    (net (code "64") (name "unconnected-(U1-G45{slash}UA_TX1-PadJ2-9)") (class "Default")
      (node (ref "U1") (pin "J2-9") (pinfunction "G45/UA_TX1_J2-9") (pintype "bidirectional"))
    )
    (net (code "65") (name "unconnected-(U1-G46{slash}UA_RX1-PadJ2-8)") (class "Default")
      (node (ref "U1") (pin "J2-8") (pinfunction "G46/UA_RX1_J2-8") (pintype "bidirectional"))
    )
    (net (code "66") (name "unconnected-(U1-USB+-PadJ1-3)") (class "Default")
      (node (ref "U1") (pin "J1-3") (pinfunction "USB+_J1-3") (pintype "bidirectional"))
    )
    (net (code "67") (name "unconnected-(U1-USB--PadJ1-4)") (class "Default")
      (node (ref "U1") (pin "J1-4") (pinfunction "USB-_J1-4") (pintype "bidirectional"))
    )
    (net (code "68") (name "unconnected-(U1-V-NET-PadJ1-8)") (class "Default")
      (node (ref "U1") (pin "J1-8") (pinfunction "V-NET_J1-8") (pintype "bidirectional"))
    )
    (net (code "69") (name "~{FACTORY_RST}") (class "Default")
      (node (ref "S2") (pin "3") (pinfunction "2_3") (pintype "passive"))
      (node (ref "U1") (pin "J1-7") (pinfunction "WDT_R/G38_J1-7") (pintype "bidirectional"))
    )
    (net (code "70") (name "~{OMEGA_RST}") (class "Default")
      (node (ref "U1") (pin "J2-16") (pinfunction "RST_J2-16") (pintype "bidirectional"))
    )
    (net (code "71") (name "~{OUT_ENABLE}") (class "Default")
      (node (ref "U1") (pin "J2-3") (pinfunction "G3/I2S/PCM_J2-3") (pintype "bidirectional"))
    )
    (net (code "72") (name "~{OUT_RESET}") (class "Default")
      (node (ref "U1") (pin "J2-5") (pinfunction "G17/U_RX2_J2-5") (pintype "bidirectional"))
    )
    (net (code "73") (name "~{PWM0_OE}") (class "Default")
      (node (ref "IC1") (pin "8") (pinfunction "PB7_8") (pintype "bidirectional"))
      (node (ref "IC2") (pin "1") (pinfunction "~{OE1}_1") (pintype "input"))
    )
    (net (code "74") (name "~{PWM1_OE}") (class "Default")
      (node (ref "IC1") (pin "7") (pinfunction "PB6_7") (pintype "bidirectional"))
      (node (ref "IC2") (pin "4") (pinfunction "~{OE2}_4") (pintype "input"))
    )
    (net (code "75") (name "~{SPI_CS_1}") (class "Default")
      (node (ref "U1") (pin "J2-6") (pinfunction "G16/U_TX2_J2-6") (pintype "bidirectional"))
    )
    (net (code "76") (name "~{SPI_CS}") (class "Default")
      (node (ref "SV2") (pin "3") (pinfunction "3_3") (pintype "passive"))
      (node (ref "U1") (pin "J2-13") (pinfunction "G6/SPI_CS1_J2-13") (pintype "bidirectional"))
    )
  )
)
